# SCH_PLC.net
KiCad netlist of a schematic drawn in Altium Designer
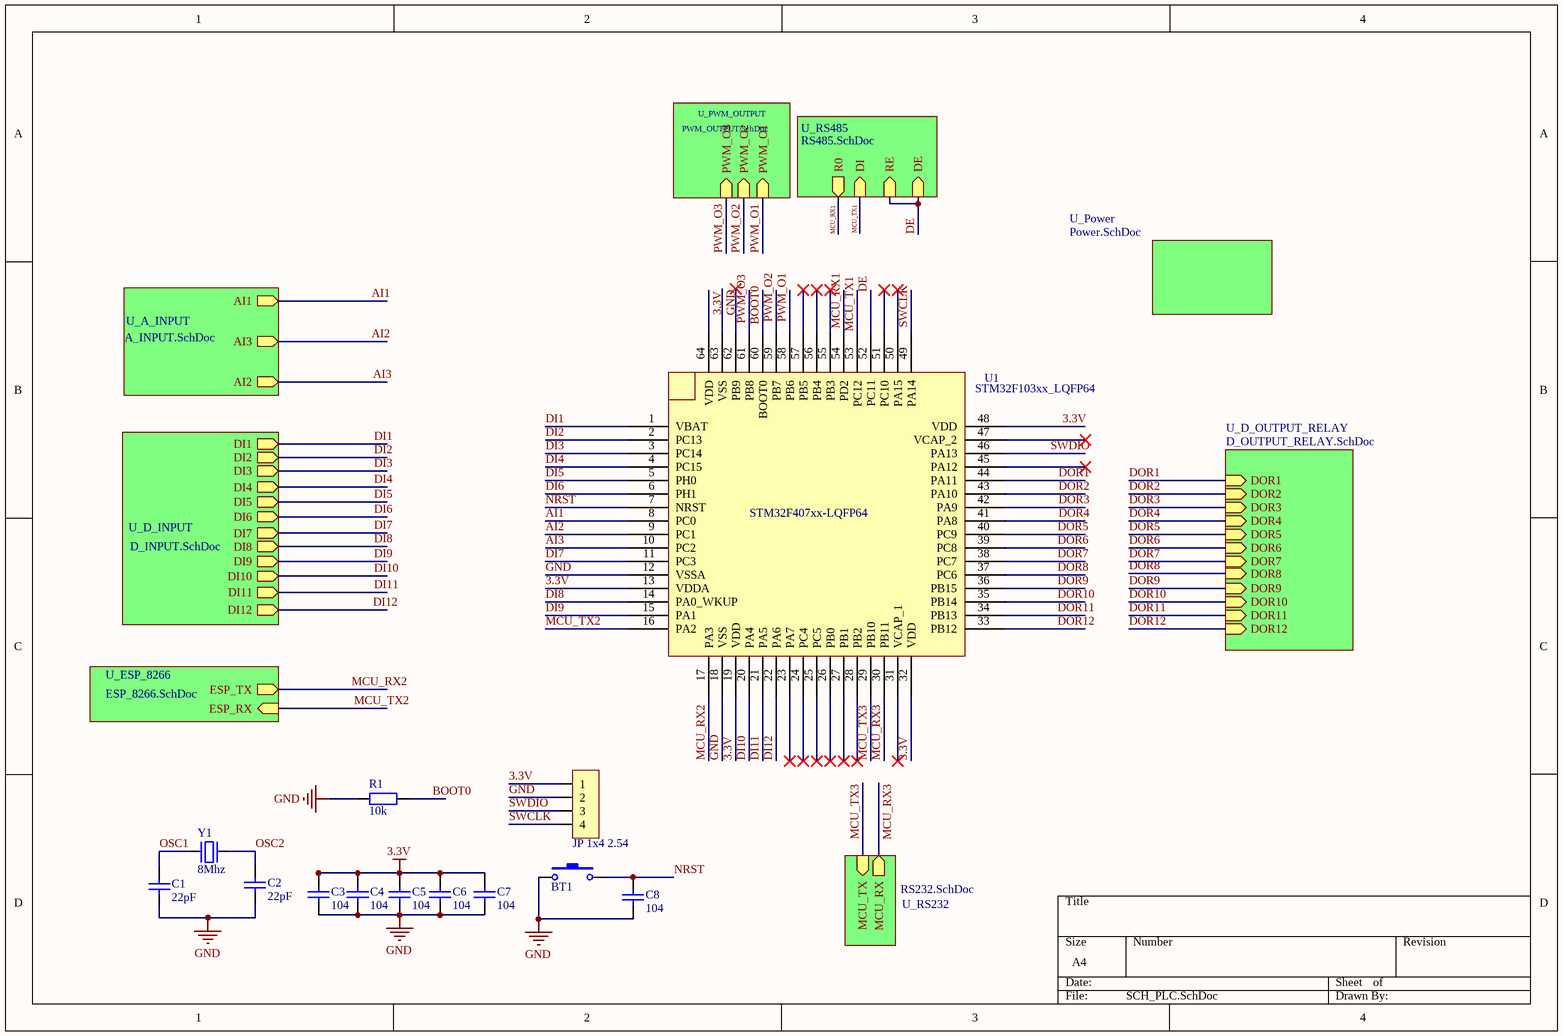
[diagram p0: SCH_PLC.SchDoc]

(export (version "E")
  (design (tool "Eeschema 10.0.6"))
  (components
    (comp (ref "BT1")
      (value "Nut Nhan 2 Chan SMD 3x6x2.5")
      (footprint "Nut Nhan 2 Chan SMD 3x6x2.5")
      (libsource (lib "Altium_Lib_by_KhueNguyenCreator") (part "Nut Nhan 2 Chan SMD 3x6x2.5"))
    )
    (comp (ref "C1")
      (value "22pF")
      (footprint "tu 0805")
      (description "Dán")
      (libsource (lib "Altium_Lib_by_KhueNguyenCreator") (part "Tu 0805 22pF 50V 10%"))
    )
    (comp (ref "C2")
      (value "22pF")
      (footprint "tu 0805")
      (description "Dán")
      (libsource (lib "Altium_Lib_by_KhueNguyenCreator") (part "Tu 0805 22pF 50V 10%"))
    )
    (comp (ref "C3")
      (value "104")
      (footprint "tu 0805")
      (description "Dán")
      (libsource (lib "Altium_Lib_by_KhueNguyenCreator") (part "Tu 0805 104 50V 10%"))
    )
    (comp (ref "C4")
      (value "104")
      (footprint "tu 0805")
      (description "Dán")
      (libsource (lib "Altium_Lib_by_KhueNguyenCreator") (part "Tu 0805 104 50V 10%"))
    )
    (comp (ref "C5")
      (value "104")
      (footprint "tu 0805")
      (description "Dán")
      (libsource (lib "Altium_Lib_by_KhueNguyenCreator") (part "Tu 0805 104 50V 10%"))
    )
    (comp (ref "C6")
      (value "104")
      (footprint "tu 0805")
      (description "Dán")
      (libsource (lib "Altium_Lib_by_KhueNguyenCreator") (part "Tu 0805 104 50V 10%"))
    )
    (comp (ref "C7")
      (value "104")
      (footprint "tu 0805")
      (description "Dán")
      (libsource (lib "Altium_Lib_by_KhueNguyenCreator") (part "Tu 0805 104 50V 10%"))
    )
    (comp (ref "C8")
      (value "104")
      (footprint "tu 0805")
      (description "Dán")
      (libsource (lib "Altium_Lib_by_KhueNguyenCreator") (part "Tu 0805 104 50V 10%"))
    )
    (comp (ref "JP1")
      (value "JP 1x4 2.54")
      (footprint "JP 1x4 DT")
      (description "Cắm")
      (libsource (lib "Altium_Lib_by_KhueNguyenCreator") (part "JP 1x4 2.54 Duc Thang"))
    )
    (comp (ref "R1")
      (value "10k")
      (footprint "tro smd 0805")
      (description "Dán")
      (libsource (lib "Altium_Lib_by_KhueNguyenCreator") (part "Tro 0805 1% 10k"))
    )
    (comp (ref "U1")
      (value "STM32F103xx_LQFP64")
      (footprint "STM32_LQFP64")
      (libsource (lib "Altium_Lib_by_KhueNguyenCreator") (part "STM32F103xx_LQFP64"))
    )
    (comp (ref "Y1")
      (value "8Mhz")
      (footprint "Thach Anh 2 chan SMD")
      (description "Crystal For all Crystal 2pin.")
      (libsource (lib "Altium_Lib_by_KhueNguyenCreator") (part "Thach Anh 2 chan SMD"))
    )
  )
  (nets
    (net (code "2") (name "/AI1") (class "Default")
      (node (ref "U1") (pin "8") (pinfunction "PC0_8") (pintype "passive"))
    )
    (net (code "3") (name "/AI2") (class "Default")
      (node (ref "U1") (pin "9") (pinfunction "PC1_9") (pintype "passive"))
    )
    (net (code "4") (name "/AI3") (class "Default")
      (node (ref "U1") (pin "10") (pinfunction "PC2_10") (pintype "passive"))
    )
    (net (code "5") (name "/BOOT0") (class "Default")
      (node (ref "R1") (pin "2") (pinfunction "2_2") (pintype "passive"))
      (node (ref "U1") (pin "60") (pinfunction "BOOT0_60") (pintype "passive"))
    )
    (net (code "6") (name "/DE") (class "Default")
      (node (ref "U1") (pin "52") (pinfunction "PC11_52") (pintype "passive"))
    )
    (net (code "7") (name "/DI1") (class "Default")
      (node (ref "U1") (pin "1") (pinfunction "VBAT_1") (pintype "passive"))
    )
    (net (code "8") (name "/DI2") (class "Default")
      (node (ref "U1") (pin "2") (pinfunction "PC13_2") (pintype "passive"))
    )
    (net (code "9") (name "/DI3") (class "Default")
      (node (ref "U1") (pin "3") (pinfunction "PC14_3") (pintype "passive"))
    )
    (net (code "10") (name "/DI4") (class "Default")
      (node (ref "U1") (pin "4") (pinfunction "PC15_4") (pintype "passive"))
    )
    (net (code "11") (name "/DI5") (class "Default")
      (node (ref "U1") (pin "5") (pinfunction "PH0_5") (pintype "passive"))
    )
    (net (code "12") (name "/DI6") (class "Default")
      (node (ref "U1") (pin "6") (pinfunction "PH1_6") (pintype "passive"))
    )
    (net (code "13") (name "/DI7") (class "Default")
      (node (ref "U1") (pin "11") (pinfunction "PC3_11") (pintype "passive"))
    )
    (net (code "14") (name "/DI8") (class "Default")
      (node (ref "U1") (pin "14") (pinfunction "PA0_WKUP_14") (pintype "passive"))
    )
    (net (code "15") (name "/DI9") (class "Default")
      (node (ref "U1") (pin "15") (pinfunction "PA1_15") (pintype "passive"))
    )
    (net (code "16") (name "/DI10") (class "Default")
      (node (ref "U1") (pin "20") (pinfunction "PA4_20") (pintype "passive"))
    )
    (net (code "17") (name "/DI11") (class "Default")
      (node (ref "U1") (pin "21") (pinfunction "PA5_21") (pintype "passive"))
    )
    (net (code "18") (name "/DI12") (class "Default")
      (node (ref "U1") (pin "22") (pinfunction "PA6_22") (pintype "passive"))
    )
    (net (code "19") (name "/DOR1") (class "Default")
      (node (ref "U1") (pin "44") (pinfunction "PA11_44") (pintype "passive"))
    )
    (net (code "20") (name "/DOR2") (class "Default")
      (node (ref "U1") (pin "43") (pinfunction "PA10_43") (pintype "passive"))
    )
    (net (code "21") (name "/DOR3") (class "Default")
      (node (ref "U1") (pin "42") (pinfunction "PA9_42") (pintype "passive"))
    )
    (net (code "22") (name "/DOR4") (class "Default")
      (node (ref "U1") (pin "41") (pinfunction "PA8_41") (pintype "passive"))
    )
    (net (code "23") (name "/DOR5") (class "Default")
      (node (ref "U1") (pin "40") (pinfunction "PC9_40") (pintype "passive"))
    )
    (net (code "24") (name "/DOR6") (class "Default")
      (node (ref "U1") (pin "39") (pinfunction "PC8_39") (pintype "passive"))
    )
    (net (code "25") (name "/DOR7") (class "Default")
      (node (ref "U1") (pin "38") (pinfunction "PC7_38") (pintype "passive"))
    )
    (net (code "26") (name "/DOR8") (class "Default")
      (node (ref "U1") (pin "37") (pinfunction "PC6_37") (pintype "passive"))
    )
    (net (code "27") (name "/DOR9") (class "Default")
      (node (ref "U1") (pin "36") (pinfunction "PB15_36") (pintype "passive"))
    )
    (net (code "28") (name "/DOR10") (class "Default")
      (node (ref "U1") (pin "35") (pinfunction "PB14_35") (pintype "passive"))
    )
    (net (code "29") (name "/DOR11") (class "Default")
      (node (ref "U1") (pin "34") (pinfunction "PB13_34") (pintype "passive"))
    )
    (net (code "30") (name "/DOR12") (class "Default")
      (node (ref "U1") (pin "33") (pinfunction "PB12_33") (pintype "passive"))
    )
    (net (code "31") (name "/MCU_RX1") (class "Default")
      (node (ref "U1") (pin "54") (pinfunction "PD2_54") (pintype "passive"))
    )
    (net (code "32") (name "/MCU_RX2") (class "Default")
      (node (ref "U1") (pin "17") (pinfunction "PA3_17") (pintype "passive"))
    )
    (net (code "33") (name "/MCU_RX3") (class "Default")
      (node (ref "U1") (pin "30") (pinfunction "PB11_30") (pintype "passive"))
    )
    (net (code "34") (name "/MCU_TX1") (class "Default")
      (node (ref "U1") (pin "53") (pinfunction "PC12_53") (pintype "passive"))
    )
    (net (code "35") (name "/MCU_TX2") (class "Default")
      (node (ref "U1") (pin "16") (pinfunction "PA2_16") (pintype "passive"))
    )
    (net (code "36") (name "/MCU_TX3") (class "Default")
      (node (ref "U1") (pin "29") (pinfunction "PB10_29") (pintype "passive"))
    )
    (net (code "37") (name "/NRST") (class "Default")
      (node (ref "BT1") (pin "2") (pinfunction "2_2") (pintype "passive"))
      (node (ref "C8") (pin "2") (pinfunction "2_2") (pintype "passive"))
      (node (ref "U1") (pin "7") (pinfunction "NRST_7") (pintype "passive"))
    )
    (net (code "38") (name "/OSC1") (class "Default")
      (node (ref "C1") (pin "1") (pinfunction "1_1") (pintype "passive"))
      (node (ref "Y1") (pin "1") (pinfunction "1_1") (pintype "passive"))
    )
    (net (code "39") (name "/OSC2") (class "Default")
      (node (ref "C2") (pin "1") (pinfunction "1_1") (pintype "passive"))
      (node (ref "Y1") (pin "2") (pinfunction "2_2") (pintype "passive"))
    )
    (net (code "40") (name "/PWM_O1") (class "Default")
      (node (ref "U1") (pin "58") (pinfunction "PB6_58") (pintype "passive"))
    )
    (net (code "41") (name "/PWM_O2") (class "Default")
      (node (ref "U1") (pin "59") (pinfunction "PB7_59") (pintype "passive"))
    )
    (net (code "42") (name "/PWM_O3") (class "Default")
      (node (ref "U1") (pin "61") (pinfunction "PB8_61") (pintype "passive"))
    )
    (net (code "43") (name "/SWCLK") (class "Default")
      (node (ref "JP1") (pin "4") (pinfunction "4_4") (pintype "passive"))
      (node (ref "U1") (pin "49") (pinfunction "PA14_49") (pintype "passive"))
    )
    (net (code "44") (name "/SWDIO") (class "Default")
      (node (ref "JP1") (pin "3") (pinfunction "3_3") (pintype "passive"))
      (node (ref "U1") (pin "46") (pinfunction "PA13_46") (pintype "passive"))
    )
    (net (code "45") (name "3.3V") (class "Default")
      (node (ref "C3") (pin "1") (pinfunction "1_1") (pintype "passive"))
      (node (ref "C4") (pin "1") (pinfunction "1_1") (pintype "passive"))
      (node (ref "C5") (pin "1") (pinfunction "1_1") (pintype "passive"))
      (node (ref "C6") (pin "2") (pinfunction "2_2") (pintype "passive"))
      (node (ref "C7") (pin "2") (pinfunction "2_2") (pintype "passive"))
      (node (ref "JP1") (pin "1") (pinfunction "1_1") (pintype "passive"))
      (node (ref "U1") (pin "13") (pinfunction "VDDA_13") (pintype "passive"))
      (node (ref "U1") (pin "19") (pinfunction "VDD_19") (pintype "passive"))
      (node (ref "U1") (pin "32") (pinfunction "VDD_32") (pintype "passive"))
      (node (ref "U1") (pin "48") (pinfunction "VDD_48") (pintype "passive"))
      (node (ref "U1") (pin "64") (pinfunction "VDD_64") (pintype "passive"))
    )
    (net (code "46") (name "GND") (class "Default")
      (node (ref "BT1") (pin "1") (pinfunction "1_1") (pintype "passive"))
      (node (ref "C1") (pin "2") (pinfunction "2_2") (pintype "passive"))
      (node (ref "C2") (pin "2") (pinfunction "2_2") (pintype "passive"))
      (node (ref "C3") (pin "2") (pinfunction "2_2") (pintype "passive"))
      (node (ref "C4") (pin "2") (pinfunction "2_2") (pintype "passive"))
      (node (ref "C5") (pin "2") (pinfunction "2_2") (pintype "passive"))
      (node (ref "C6") (pin "1") (pinfunction "1_1") (pintype "passive"))
      (node (ref "C7") (pin "1") (pinfunction "1_1") (pintype "passive"))
      (node (ref "C8") (pin "1") (pinfunction "1_1") (pintype "passive"))
      (node (ref "JP1") (pin "2") (pinfunction "2_2") (pintype "passive"))
      (node (ref "R1") (pin "1") (pinfunction "1_1") (pintype "passive"))
      (node (ref "U1") (pin "12") (pinfunction "VSSA_12") (pintype "passive"))
      (node (ref "U1") (pin "18") (pinfunction "VSS_18") (pintype "passive"))
      (node (ref "U1") (pin "63") (pinfunction "VSS_63") (pintype "passive"))
    )
    (net (code "47") (name "unconnected-(U1-PA7-Pad23)") (class "Default")
      (node (ref "U1") (pin "23") (pinfunction "PA7_23") (pintype "passive+no_connect"))
    )
    (net (code "48") (name "unconnected-(U1-PA12-Pad45)") (class "Default")
      (node (ref "U1") (pin "45") (pinfunction "PA12_45") (pintype "passive+no_connect"))
    )
    (net (code "49") (name "unconnected-(U1-PA15-Pad50)") (class "Default")
      (node (ref "U1") (pin "50") (pinfunction "PA15_50") (pintype "passive+no_connect"))
    )
    (net (code "50") (name "unconnected-(U1-PB0-Pad26)") (class "Default")
      (node (ref "U1") (pin "26") (pinfunction "PB0_26") (pintype "passive+no_connect"))
    )
    (net (code "51") (name "unconnected-(U1-PB1-Pad27)") (class "Default")
      (node (ref "U1") (pin "27") (pinfunction "PB1_27") (pintype "passive+no_connect"))
    )
    (net (code "52") (name "unconnected-(U1-PB2-Pad28)") (class "Default")
      (node (ref "U1") (pin "28") (pinfunction "PB2_28") (pintype "passive+no_connect"))
    )
    (net (code "53") (name "unconnected-(U1-PB3-Pad55)") (class "Default")
      (node (ref "U1") (pin "55") (pinfunction "PB3_55") (pintype "passive+no_connect"))
    )
    (net (code "54") (name "unconnected-(U1-PB4-Pad56)") (class "Default")
      (node (ref "U1") (pin "56") (pinfunction "PB4_56") (pintype "passive+no_connect"))
    )
    (net (code "55") (name "unconnected-(U1-PB5-Pad57)") (class "Default")
      (node (ref "U1") (pin "57") (pinfunction "PB5_57") (pintype "passive+no_connect"))
    )
    (net (code "56") (name "unconnected-(U1-PB9-Pad62)") (class "Default")
      (node (ref "U1") (pin "62") (pinfunction "PB9_62") (pintype "passive+no_connect"))
    )
    (net (code "57") (name "unconnected-(U1-PC4-Pad24)") (class "Default")
      (node (ref "U1") (pin "24") (pinfunction "PC4_24") (pintype "passive+no_connect"))
    )
    (net (code "58") (name "unconnected-(U1-PC5-Pad25)") (class "Default")
      (node (ref "U1") (pin "25") (pinfunction "PC5_25") (pintype "passive+no_connect"))
    )
    (net (code "59") (name "unconnected-(U1-PC10-Pad51)") (class "Default")
      (node (ref "U1") (pin "51") (pinfunction "PC10_51") (pintype "passive+no_connect"))
    )
    (net (code "60") (name "unconnected-(U1-VCAP_1-Pad31)") (class "Default")
      (node (ref "U1") (pin "31") (pinfunction "VCAP_1_31") (pintype "passive+no_connect"))
    )
    (net (code "61") (name "unconnected-(U1-VCAP_2-Pad47)") (class "Default")
      (node (ref "U1") (pin "47") (pinfunction "VCAP_2_47") (pintype "passive+no_connect"))
    )
  )
)
